# Deneigus_Controle_Soufflante.net
KiCad netlist of a schematic drawn in Altium Designer
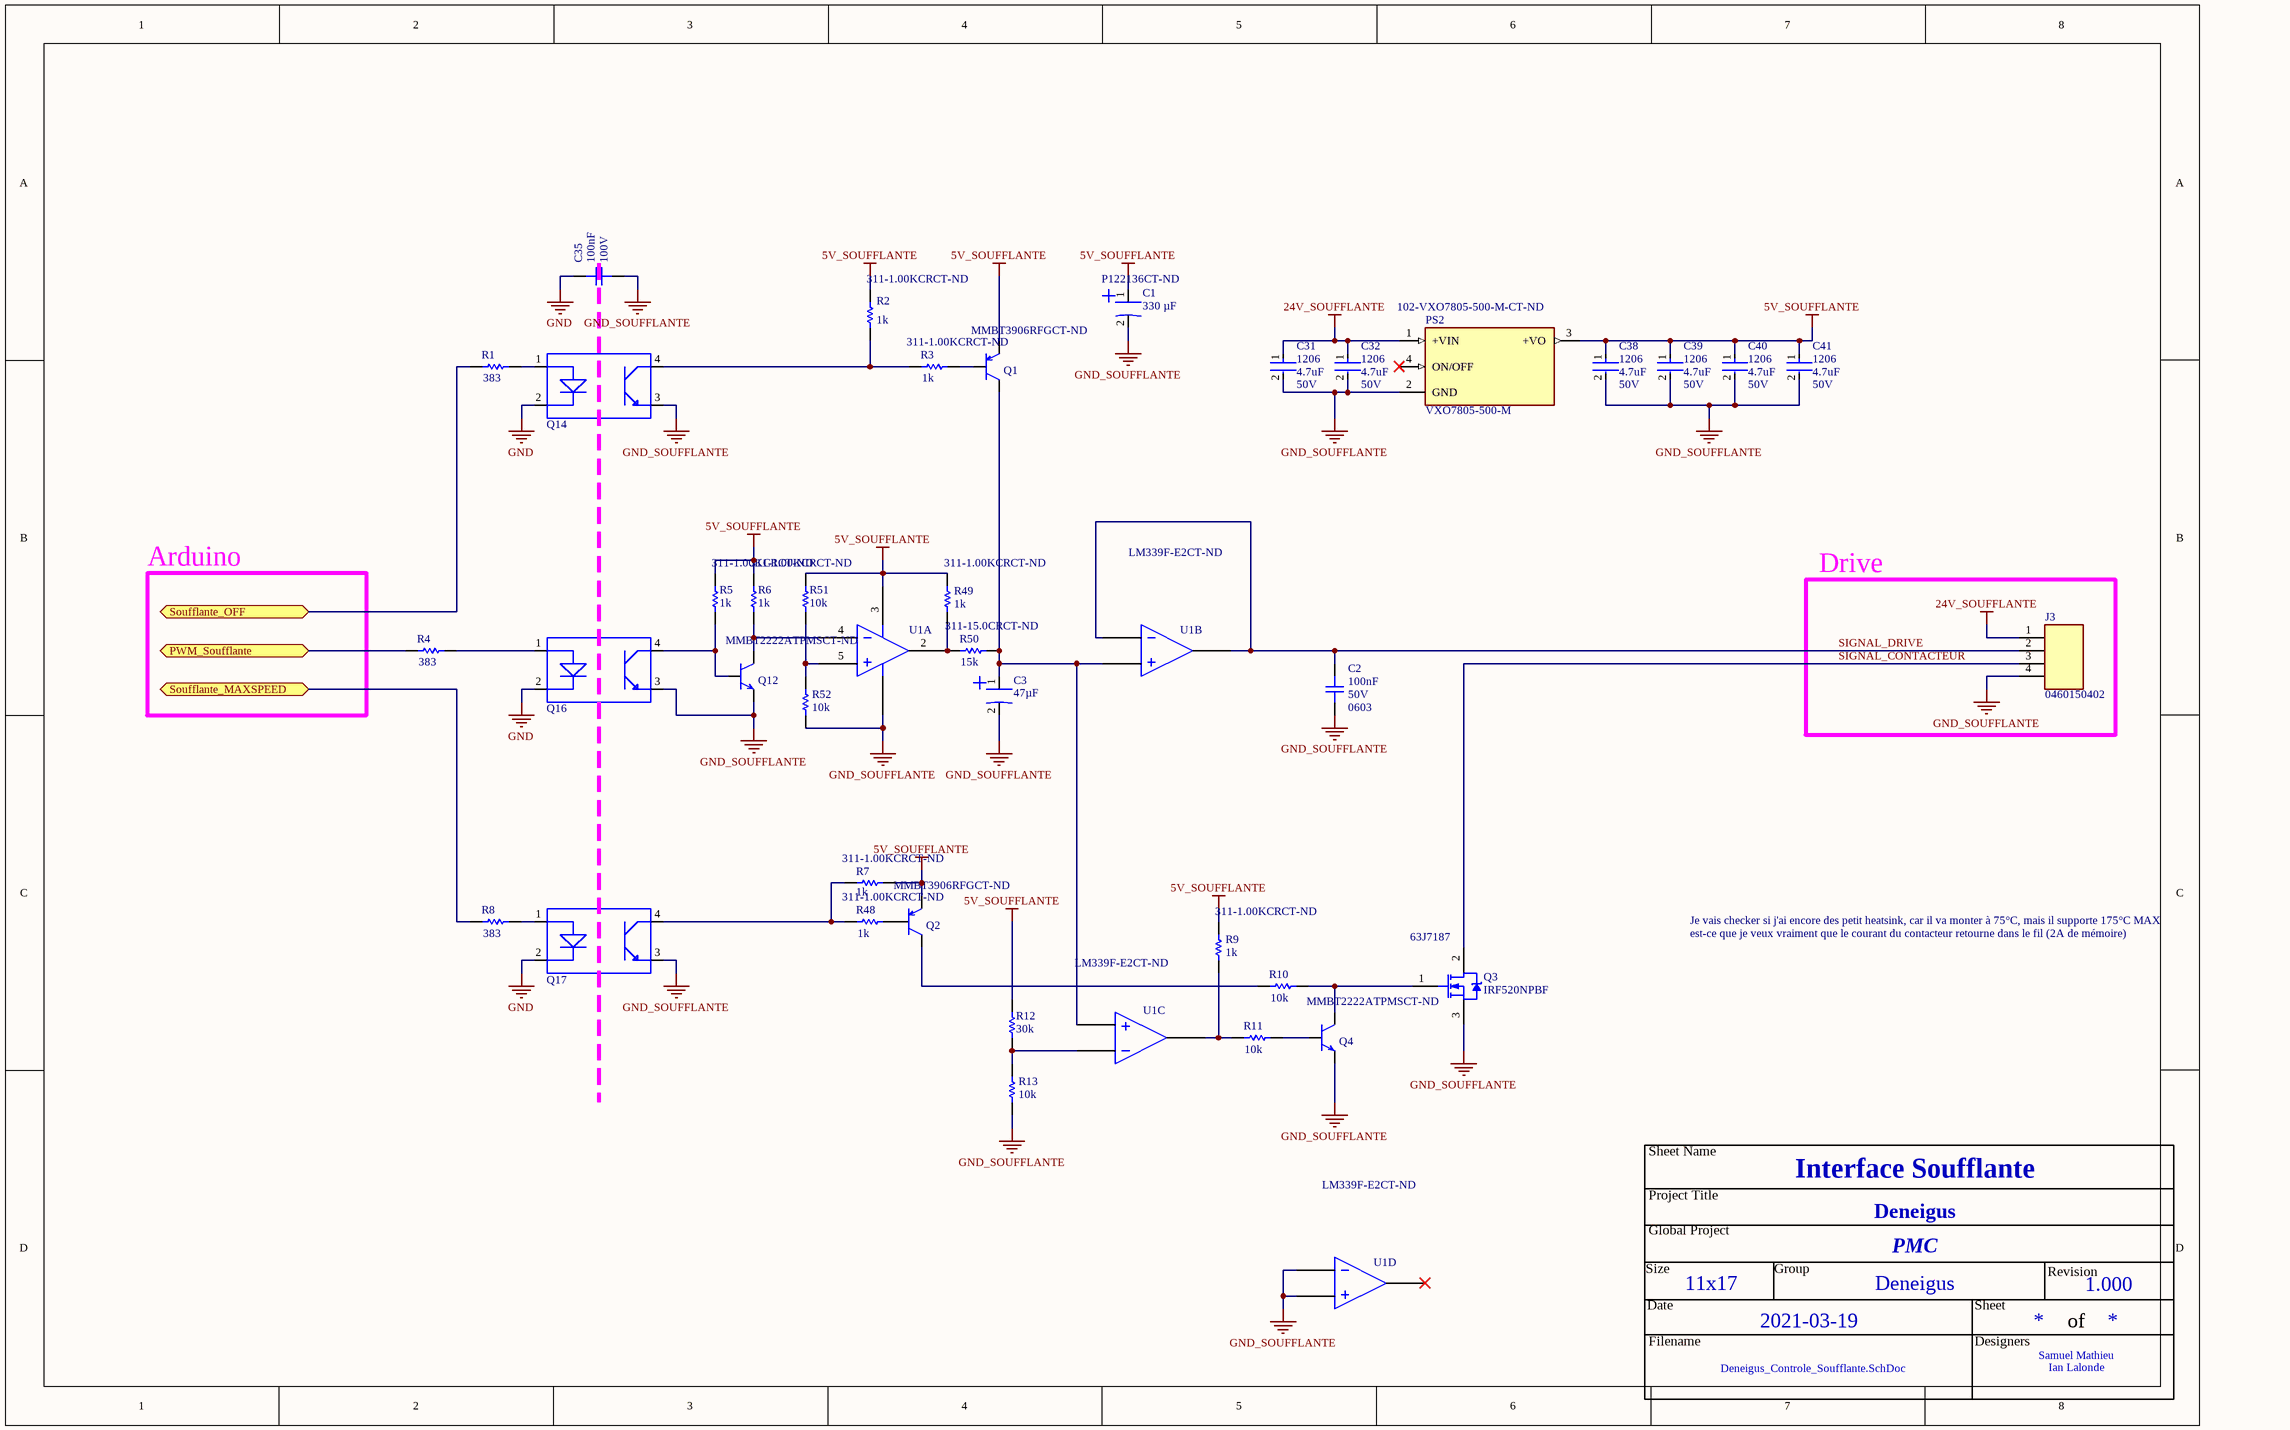
[diagram p0: Deneigus_Controle_Soufflante.SchDoc]

(export (version "E")
  (design (tool "Eeschema 10.0.6"))
  (components
    (comp (ref "C1")
      (value "330 µF")
      (footprint "330uF (10.3x10.3mm)")
      (fields
        (field (name "MFG") "Würth Elektronik")
        (field (name "MFG PART NUMBER") "875105344006")
        (field (name "SUPPLIER PART NUMBER 1") "P122136CT-ND")
        (field (name "Comment") "CAP ALUM POLY 47UF 20% 16V SMD")
      )
      (libsource (lib "S7CAS-APP1") (part "47µF SMD"))
    )
    (comp (ref "C2")
      (value "100nF")
      (footprint "CAP_0603")
      (description "CAP - 0603")
      (fields
        (field (name "VOLTAGE") "50V")
        (field (name "PACKAGE") "0603")
        (field (name "CREATEDBY") "Jonathan Bouchard")
      )
      (libsource (lib "S7CAS_LIB2021") (part "CAP - 0603"))
    )
    (comp (ref "C3")
      (value "47µF")
      (footprint "47uF")
      (fields
        (field (name "MFG") "Würth Elektronik")
        (field (name "MFG PART NUMBER") "875105344006")
        (field (name "Comment") "CAP ALUM POLY 47UF 20% 16V SMD")
      )
      (libsource (lib "S7CAS-APP1") (part "47µF SMD"))
    )
    (comp (ref "C31")
      (value "CL31B475KBHNFNE")
      (footprint "FP-CL31-IPC_C")
      (description "Cap Ceramic 4.7uF 50V X7R ±10% SMD 1206 +125°C Embossed T/R")
      (fields
        (field (name "CASE/PACKAGE") "1206")
        (field (name "VOLTAGE RATING") "50V")
        (field (name "TOLERANCE") "10%")
        (field (name "CAPACITANCE") "4.7uF")
      )
      (libsource (lib "Altium Content Vault") (part "b4654b650e69147ec39a6b967a45e02"))
    )
    (comp (ref "C32")
      (value "CL31B475KBHNFNE")
      (footprint "FP-CL31-IPC_C")
      (description "Cap Ceramic 4.7uF 50V X7R ±10% SMD 1206 +125°C Embossed T/R")
      (fields
        (field (name "CASE/PACKAGE") "1206")
        (field (name "VOLTAGE RATING") "50V")
        (field (name "TOLERANCE") "10%")
        (field (name "CAPACITANCE") "4.7uF")
      )
      (libsource (lib "Altium Content Vault") (part "b4654b650e69147ec39a6b967a45e02"))
    )
    (comp (ref "C35")
      (value "100nF")
      (footprint "CAP_0805")
      (description "CAP - 0805")
      (fields
        (field (name "MFG") "Murata Electronics")
        (field (name "MFG PART NUMBER") "GRM21BR61H106ME43L")
        (field (name "VOLTAGE") "100V")
        (field (name "CREATEDBY") "Jonathan Bouchard")
      )
      (libsource (lib "S7CAS_LIB2021(1)") (part "CAP - 0805"))
    )
    (comp (ref "C38")
      (value "CL31B475KBHNFNE")
      (footprint "FP-CL31-IPC_C")
      (description "Cap Ceramic 4.7uF 50V X7R ±10% SMD 1206 +125°C Embossed T/R")
      (fields
        (field (name "CASE/PACKAGE") "1206")
        (field (name "VOLTAGE RATING") "50V")
        (field (name "TOLERANCE") "10%")
        (field (name "CAPACITANCE") "4.7uF")
      )
      (libsource (lib "Altium Content Vault") (part "b4654b650e69147ec39a6b967a45e02"))
    )
    (comp (ref "C39")
      (value "CL31B475KBHNFNE")
      (footprint "FP-CL31-IPC_C")
      (description "Cap Ceramic 4.7uF 50V X7R ±10% SMD 1206 +125°C Embossed T/R")
      (fields
        (field (name "CASE/PACKAGE") "1206")
        (field (name "VOLTAGE RATING") "50V")
        (field (name "TOLERANCE") "10%")
        (field (name "CAPACITANCE") "4.7uF")
      )
      (libsource (lib "Altium Content Vault") (part "b4654b650e69147ec39a6b967a45e02"))
    )
    (comp (ref "C40")
      (value "CL31B475KBHNFNE")
      (footprint "FP-CL31-IPC_C")
      (description "Cap Ceramic 4.7uF 50V X7R ±10% SMD 1206 +125°C Embossed T/R")
      (fields
        (field (name "CASE/PACKAGE") "1206")
        (field (name "VOLTAGE RATING") "50V")
        (field (name "TOLERANCE") "10%")
        (field (name "CAPACITANCE") "4.7uF")
      )
      (libsource (lib "Altium Content Vault") (part "b4654b650e69147ec39a6b967a45e02"))
    )
    (comp (ref "C41")
      (value "CL31B475KBHNFNE")
      (footprint "FP-CL31-IPC_C")
      (description "Cap Ceramic 4.7uF 50V X7R ±10% SMD 1206 +125°C Embossed T/R")
      (fields
        (field (name "CASE/PACKAGE") "1206")
        (field (name "VOLTAGE RATING") "50V")
        (field (name "TOLERANCE") "10%")
        (field (name "CAPACITANCE") "4.7uF")
      )
      (libsource (lib "Altium Content Vault") (part "b4654b650e69147ec39a6b967a45e02"))
    )
    (comp (ref "J3")
      (value "0460150402")
      (footprint "Molex_4PIN")
      (libsource (lib "S7CAS-APP1") (part "Molex_4PIN"))
    )
    (comp (ref "PS2")
      (value "VXO7805-500-M")
      (footprint "SnapEDApcb:CONV_VXO7805-500-M")
      (description "500 mA Output Current, 4.75~36 Vdc Input, SMT, Non-Isolated, Dc-Dc Converter")
      (fields
        (field (name "MF") "CUI Inc.")
        (field (name "SUPPLIER PART NUMBER 1") "102-VXO7805-500-M-CT-ND")
      )
      (libsource (lib "VXO7805-500-M") (part "VXO7805-500-M"))
    )
    (comp (ref "Q1")
      (value "TRANS PNP 40V 0.2A SOT23")
      (footprint "SOT-23")
      (description "Trans GP BJT PNP 40V 0.2A 3-Pin SOT-23 T/R")
      (fields
        (field (name "MANUFACTURER") "MCC")
        (field (name "MANUFACTURER PART NUMBER") "MMBT3906-TP")
        (field (name "SUPPLIER PART NUMBER 1") "MMBT3906RFGCT-ND")
      )
      (libsource (lib "S7CAS-APP1") (part "PNP 3906 SMD"))
    )
    (comp (ref "Q2")
      (value "TRANS PNP 40V 0.2A SOT23")
      (footprint "SOT-23")
      (description "Trans GP BJT PNP 40V 0.2A 3-Pin SOT-23 T/R")
      (fields
        (field (name "MANUFACTURER") "MCC")
        (field (name "MANUFACTURER PART NUMBER") "MMBT3906-TP")
        (field (name "SUPPLIER PART NUMBER 1") "MMBT3906RFGCT-ND")
      )
      (libsource (lib "S7CAS-APP1") (part "PNP 3906 SMD"))
    )
    (comp (ref "Q3")
      (value "IRF520NPBF")
      (footprint "INTR-TO-220AB-3")
      (description "HEXFET(R) Power MOSFET, 100 V, 9.7 A, 0.2 Ohm, -55 to 175 degC, 3-Pin FM (TO-220AB), RoHS, Tube")
      (fields
        (field (name "POWER") "48W")
        (field (name "MANUFACTURER") "International Rectifier")
        (field (name "SUPPLIER PART NUMBER 1") "63J7187")
      )
      (libsource (lib "Université de Sherbrooke") (part "NEMOS-GDS-3_B"))
    )
    (comp (ref "Q4")
      (value "TRANS NPN 40V 0.2A SOT23")
      (footprint "SOT-23")
      (description "Transistor: 200mA 200mW NPN General-Purpose Amplifier, SOT-23, 7IN. Reel")
      (fields
        (field (name "MANUFACTURER") "MCC")
        (field (name "MANUFACTURER PART NUMBER") "MMBT3904-TP")
        (field (name "SUPPLIER PART NUMBER 1") "MMBT2222ATPMSCT-ND")
      )
      (libsource (lib "S7CAS-APP1") (part "NPN 3904 SMD"))
    )
    (comp (ref "Q12")
      (value "TRANS NPN 40V 0.2A SOT23")
      (footprint "SOT-23")
      (description "Transistor: 200mA 200mW NPN General-Purpose Amplifier, SOT-23, 7IN. Reel")
      (fields
        (field (name "MANUFACTURER") "MCC")
        (field (name "MANUFACTURER PART NUMBER") "MMBT3904-TP")
        (field (name "SUPPLIER PART NUMBER 1") "MMBT2222ATPMSCT-ND")
      )
      (libsource (lib "S7CAS-APP1") (part "NPN 3904 SMD"))
    )
    (comp (ref "Q14")
      (value "WL-OCPT OPTOCOUPLER PHOTOTRANSIS")
      (footprint "WL-OCPT OPTOCOUPLER PHOTOTRANSIS")
      (description "Optoisolator Transistor Output 3750Vrms 1 Channel 4-SOP")
      (libsource (lib "S7CAS-APP1") (part "WL-OCPT OPTOCOUPLER PHOTOTRANSIS"))
    )
    (comp (ref "Q16")
      (value "WL-OCPT OPTOCOUPLER PHOTOTRANSIS")
      (footprint "WL-OCPT OPTOCOUPLER PHOTOTRANSIS")
      (description "Optoisolator Transistor Output 3750Vrms 1 Channel 4-SOP")
      (libsource (lib "S7CAS-APP1") (part "WL-OCPT OPTOCOUPLER PHOTOTRANSIS"))
    )
    (comp (ref "Q17")
      (value "WL-OCPT OPTOCOUPLER PHOTOTRANSIS")
      (footprint "WL-OCPT OPTOCOUPLER PHOTOTRANSIS")
      (description "Optoisolator Transistor Output 3750Vrms 1 Channel 4-SOP")
      (libsource (lib "S7CAS-APP1") (part "WL-OCPT OPTOCOUPLER PHOTOTRANSIS"))
    )
    (comp (ref "R1")
      (value "383")
      (footprint "RES_0805")
      (description "Resistor")
      (fields (field (name "Comment") "Res1") (field (name "PUBLISHER") "Altium Limited"))
      (libsource (lib "Miscellaneous Devices") (part "Res1"))
    )
    (comp (ref "R2")
      (value "1k")
      (footprint "RES_0805")
      (description "Resistor")
      (fields
        (field (name "SUPPLIER PART NUMBER 1") "311-1.00KCRCT-ND")
        (field (name "Comment") "Res1")
        (field (name "PUBLISHER") "Altium Limited")
      )
      (libsource (lib "Miscellaneous Devices") (part "Res1"))
    )
    (comp (ref "R3")
      (value "1k")
      (footprint "RES_0805")
      (description "Resistor")
      (fields
        (field (name "SUPPLIER PART NUMBER 1") "311-1.00KCRCT-ND")
        (field (name "Comment") "Res1")
        (field (name "PUBLISHER") "Altium Limited")
      )
      (libsource (lib "Miscellaneous Devices") (part "Res1"))
    )
    (comp (ref "R4")
      (value "383")
      (footprint "RES_0805")
      (description "Resistor")
      (fields (field (name "Comment") "Res1") (field (name "PUBLISHER") "Altium Limited"))
      (libsource (lib "Miscellaneous Devices") (part "Res1"))
    )
    (comp (ref "R5")
      (value "1k")
      (footprint "RES_0805")
      (description "Resistor")
      (fields
        (field (name "SUPPLIER PART NUMBER 1") "311-1.00KCRCT-ND")
        (field (name "Comment") "Res1")
        (field (name "PUBLISHER") "Altium Limited")
      )
      (libsource (lib "Miscellaneous Devices") (part "Res1"))
    )
    (comp (ref "R6")
      (value "1k")
      (footprint "RES_0805")
      (description "Resistor")
      (fields
        (field (name "SUPPLIER PART NUMBER 1") "311-1.00KCRCT-ND")
        (field (name "Comment") "Res1")
        (field (name "PUBLISHER") "Altium Limited")
      )
      (libsource (lib "Miscellaneous Devices") (part "Res1"))
    )
    (comp (ref "R7")
      (value "1k")
      (footprint "RES_0805")
      (description "Resistor")
      (fields
        (field (name "SUPPLIER PART NUMBER 1") "311-1.00KCRCT-ND")
        (field (name "Comment") "Res1")
        (field (name "PUBLISHER") "Altium Limited")
      )
      (libsource (lib "Miscellaneous Devices") (part "Res1"))
    )
    (comp (ref "R8")
      (value "383")
      (footprint "RES_0805")
      (description "Resistor")
      (fields (field (name "Comment") "Res1") (field (name "PUBLISHER") "Altium Limited"))
      (libsource (lib "Miscellaneous Devices") (part "Res1"))
    )
    (comp (ref "R9")
      (value "1k")
      (footprint "RES_0805")
      (description "Resistor")
      (fields
        (field (name "SUPPLIER PART NUMBER 1") "311-1.00KCRCT-ND")
        (field (name "Comment") "Res1")
        (field (name "PUBLISHER") "Altium Limited")
      )
      (libsource (lib "Miscellaneous Devices") (part "Res1"))
    )
    (comp (ref "R10")
      (value "10k")
      (footprint "RES_0805")
      (description "Resistor")
      (fields (field (name "Comment") "Res1") (field (name "PUBLISHER") "Altium Limited"))
      (libsource (lib "Miscellaneous Devices") (part "Res1"))
    )
    (comp (ref "R11")
      (value "10k")
      (footprint "RES_0805")
      (description "Resistor")
      (fields (field (name "Comment") "Res1") (field (name "PUBLISHER") "Altium Limited"))
      (libsource (lib "Miscellaneous Devices") (part "Res1"))
    )
    (comp (ref "R12")
      (value "30k")
      (footprint "RES_0805")
      (description "Resistor")
      (fields (field (name "Comment") "Res1") (field (name "PUBLISHER") "Altium Limited"))
      (libsource (lib "Miscellaneous Devices") (part "Res1"))
    )
    (comp (ref "R13")
      (value "10k")
      (footprint "RES_0805")
      (description "Resistor")
      (fields (field (name "Comment") "Res1") (field (name "PUBLISHER") "Altium Limited"))
      (libsource (lib "Miscellaneous Devices") (part "Res1"))
    )
    (comp (ref "R48")
      (value "1k")
      (footprint "RES_0805")
      (description "Resistor")
      (fields
        (field (name "SUPPLIER PART NUMBER 1") "311-1.00KCRCT-ND")
        (field (name "Comment") "Res1")
        (field (name "PUBLISHER") "Altium Limited")
      )
      (libsource (lib "Miscellaneous Devices") (part "Res1"))
    )
    (comp (ref "R49")
      (value "1k")
      (footprint "RES_0805")
      (description "Resistor")
      (fields
        (field (name "SUPPLIER PART NUMBER 1") "311-1.00KCRCT-ND")
        (field (name "Comment") "Res1")
        (field (name "PUBLISHER") "Altium Limited")
      )
      (libsource (lib "Miscellaneous Devices") (part "Res1"))
    )
    (comp (ref "R50")
      (value "15k")
      (footprint "RES_0805")
      (description "Resistor")
      (fields
        (field (name "SUPPLIER PART NUMBER 1") "311-15.0CRCT-ND")
        (field (name "Comment") "Res1")
        (field (name "PUBLISHER") "Altium Limited")
      )
      (libsource (lib "Miscellaneous Devices") (part "Res1"))
    )
    (comp (ref "R51")
      (value "10k")
      (footprint "RES_0805")
      (description "Resistor")
      (fields (field (name "Comment") "Res1") (field (name "PUBLISHER") "Altium Limited"))
      (libsource (lib "Miscellaneous Devices") (part "Res1"))
    )
    (comp (ref "R52")
      (value "10k")
      (footprint "RES_0805")
      (description "Resistor")
      (fields (field (name "Comment") "Res1") (field (name "PUBLISHER") "Altium Limited"))
      (libsource (lib "Miscellaneous Devices") (part "Res1"))
    )
    (comp (ref "U1")
      (value "LM339")
      (footprint "SOP14")
      (description "Comparator Quad ±16V/32V 14-Pin SOP T/R")
      (fields
        (field (name "VOLTAGE") "1.14 V ~ 1.26 V")
        (field (name "MFG") "Rohm Semiconductor")
        (field (name "SUPPLIER PART NUMBER 2") "LM339F-E2CT-ND")
        (field (name "CREATEDBY") "Samuel Mathieu")
      )
      (libsource (lib "S7CAS-APP1") (part "LM339"))
    )
  )
  (nets
    (net (code "1") (name "/PWM_Soufflante") (class "Default")
      (node (ref "R4") (pin "1") (pinfunction "1_1") (pintype "passive"))
    )
    (net (code "2") (name "/SIGNAL_CONTACTEUR") (class "Default")
      (node (ref "J3") (pin "3") (pinfunction "3_3") (pintype "passive"))
      (node (ref "Q3") (pin "2") (pinfunction "D_2") (pintype "passive"))
    )
    (net (code "3") (name "/SIGNAL_DRIVE") (class "Default")
      (node (ref "C2") (pin "2") (pinfunction "2_2") (pintype "passive"))
      (node (ref "J3") (pin "2") (pinfunction "2_2") (pintype "passive"))
      (node (ref "U1") (pin "1") (pinfunction "1_1") (pintype "passive"))
      (node (ref "U1") (pin "6") (pinfunction "6_6") (pintype "passive"))
    )
    (net (code "4") (name "/Soufflante_MAXSPEED") (class "Default")
      (node (ref "R8") (pin "1") (pinfunction "1_1") (pintype "passive"))
    )
    (net (code "5") (name "/Soufflante_OFF") (class "Default")
      (node (ref "R1") (pin "1") (pinfunction "1_1") (pintype "passive"))
    )
    (net (code "6") (name "5V_SOUFFLANTE") (class "Default")
      (node (ref "C1") (pin "1") (pinfunction "1_1") (pintype "passive"))
      (node (ref "C38") (pin "1") (pinfunction "1_1") (pintype "passive"))
      (node (ref "C39") (pin "1") (pinfunction "1_1") (pintype "passive"))
      (node (ref "C40") (pin "1") (pinfunction "1_1") (pintype "passive"))
      (node (ref "C41") (pin "1") (pinfunction "1_1") (pintype "passive"))
      (node (ref "PS2") (pin "3") (pinfunction "+VO_3") (pintype "output"))
      (node (ref "Q1") (pin "2") (pinfunction "2_2") (pintype "passive"))
      (node (ref "Q2") (pin "2") (pinfunction "2_2") (pintype "passive"))
      (node (ref "R12") (pin "2") (pinfunction "2_2") (pintype "passive"))
      (node (ref "R2") (pin "1") (pinfunction "1_1") (pintype "passive"))
      (node (ref "R49") (pin "1") (pinfunction "1_1") (pintype "passive"))
      (node (ref "R5") (pin "2") (pinfunction "2_2") (pintype "passive"))
      (node (ref "R51") (pin "2") (pinfunction "2_2") (pintype "passive"))
      (node (ref "R6") (pin "2") (pinfunction "2_2") (pintype "passive"))
      (node (ref "R7") (pin "1") (pinfunction "1_1") (pintype "passive"))
      (node (ref "R9") (pin "2") (pinfunction "2_2") (pintype "passive"))
      (node (ref "U1") (pin "3") (pinfunction "3_3") (pintype "passive"))
    )
    (net (code "7") (name "24V_SOUFFLANTE") (class "Default")
      (node (ref "C31") (pin "1") (pinfunction "1_1") (pintype "passive"))
      (node (ref "C32") (pin "1") (pinfunction "1_1") (pintype "passive"))
      (node (ref "J3") (pin "1") (pinfunction "1_1") (pintype "passive"))
      (node (ref "PS2") (pin "1") (pinfunction "+VIN_1") (pintype "input"))
    )
    (net (code "8") (name "GND") (class "Default")
      (node (ref "C35") (pin "2") (pinfunction "2_2") (pintype "passive"))
      (node (ref "Q14") (pin "2") (pinfunction "2_2") (pintype "passive"))
      (node (ref "Q16") (pin "2") (pinfunction "2_2") (pintype "passive"))
      (node (ref "Q17") (pin "2") (pinfunction "2_2") (pintype "passive"))
    )
    (net (code "9") (name "GND_SOUFFLANTE") (class "Default")
      (node (ref "C1") (pin "2") (pinfunction "2_2") (pintype "passive"))
      (node (ref "C2") (pin "1") (pinfunction "1_1") (pintype "passive"))
      (node (ref "C3") (pin "2") (pinfunction "2_2") (pintype "passive"))
      (node (ref "C31") (pin "2") (pinfunction "2_2") (pintype "passive"))
      (node (ref "C32") (pin "2") (pinfunction "2_2") (pintype "passive"))
      (node (ref "C35") (pin "1") (pinfunction "1_1") (pintype "passive"))
      (node (ref "C38") (pin "2") (pinfunction "2_2") (pintype "passive"))
      (node (ref "C39") (pin "2") (pinfunction "2_2") (pintype "passive"))
      (node (ref "C40") (pin "2") (pinfunction "2_2") (pintype "passive"))
      (node (ref "C41") (pin "2") (pinfunction "2_2") (pintype "passive"))
      (node (ref "J3") (pin "4") (pinfunction "4_4") (pintype "passive"))
      (node (ref "PS2") (pin "2") (pinfunction "GND_2") (pintype "power_in"))
      (node (ref "Q12") (pin "2") (pinfunction "2_2") (pintype "passive"))
      (node (ref "Q14") (pin "3") (pinfunction "3_3") (pintype "passive"))
      (node (ref "Q16") (pin "3") (pinfunction "3_3") (pintype "passive"))
      (node (ref "Q17") (pin "3") (pinfunction "3_3") (pintype "passive"))
      (node (ref "Q3") (pin "3") (pinfunction "S_3") (pintype "passive"))
      (node (ref "Q4") (pin "2") (pinfunction "2_2") (pintype "passive"))
      (node (ref "R13") (pin "1") (pinfunction "1_1") (pintype "passive"))
      (node (ref "R52") (pin "1") (pinfunction "1_1") (pintype "passive"))
      (node (ref "U1") (pin "10") (pinfunction "10_10") (pintype "passive"))
      (node (ref "U1") (pin "11") (pinfunction "11_11") (pintype "passive"))
      (node (ref "U1") (pin "12") (pinfunction "12_12") (pintype "passive"))
    )
    (net (code "10") (name "Net-(C3-Pad1)") (class "Default")
      (node (ref "C3") (pin "1") (pinfunction "1_1") (pintype "passive"))
      (node (ref "Q1") (pin "3") (pinfunction "3_3") (pintype "passive"))
      (node (ref "R50") (pin "2") (pinfunction "2_2") (pintype "passive"))
      (node (ref "U1") (pin "7") (pinfunction "7_7") (pintype "passive"))
      (node (ref "U1") (pin "9") (pinfunction "9_9") (pintype "passive"))
    )
    (net (code "11") (name "Net-(Q1-Pad1)") (class "Default")
      (node (ref "Q1") (pin "1") (pinfunction "1_1") (pintype "passive"))
      (node (ref "R3") (pin "2") (pinfunction "2_2") (pintype "passive"))
    )
    (net (code "12") (name "Net-(Q2-Pad1)") (class "Default")
      (node (ref "Q2") (pin "1") (pinfunction "1_1") (pintype "passive"))
      (node (ref "R48") (pin "2") (pinfunction "2_2") (pintype "passive"))
    )
    (net (code "13") (name "Net-(Q2-Pad3)") (class "Default")
      (node (ref "Q2") (pin "3") (pinfunction "3_3") (pintype "passive"))
      (node (ref "R10") (pin "2") (pinfunction "2_2") (pintype "passive"))
    )
    (net (code "14") (name "Net-(Q3-G)") (class "Default")
      (node (ref "Q3") (pin "1") (pinfunction "G_1") (pintype "passive"))
      (node (ref "Q4") (pin "3") (pinfunction "3_3") (pintype "passive"))
      (node (ref "R10") (pin "1") (pinfunction "1_1") (pintype "passive"))
    )
    (net (code "15") (name "Net-(Q4-Pad1)") (class "Default")
      (node (ref "Q4") (pin "1") (pinfunction "1_1") (pintype "passive"))
      (node (ref "R11") (pin "2") (pinfunction "2_2") (pintype "passive"))
    )
    (net (code "16") (name "Net-(Q12-Pad1)") (class "Default")
      (node (ref "Q12") (pin "1") (pinfunction "1_1") (pintype "passive"))
      (node (ref "Q16") (pin "4") (pinfunction "4_4") (pintype "passive"))
      (node (ref "R5") (pin "1") (pinfunction "1_1") (pintype "passive"))
    )
    (net (code "17") (name "Net-(Q12-Pad3)") (class "Default")
      (node (ref "Q12") (pin "3") (pinfunction "3_3") (pintype "passive"))
      (node (ref "R6") (pin "1") (pinfunction "1_1") (pintype "passive"))
      (node (ref "U1") (pin "4") (pinfunction "4_4") (pintype "passive"))
    )
    (net (code "18") (name "Net-(Q14-Pad1)") (class "Default")
      (node (ref "Q14") (pin "1") (pinfunction "1_1") (pintype "passive"))
      (node (ref "R1") (pin "2") (pinfunction "2_2") (pintype "passive"))
    )
    (net (code "19") (name "Net-(Q14-Pad4)") (class "Default")
      (node (ref "Q14") (pin "4") (pinfunction "4_4") (pintype "passive"))
      (node (ref "R2") (pin "2") (pinfunction "2_2") (pintype "passive"))
      (node (ref "R3") (pin "1") (pinfunction "1_1") (pintype "passive"))
    )
    (net (code "20") (name "Net-(Q16-Pad1)") (class "Default")
      (node (ref "Q16") (pin "1") (pinfunction "1_1") (pintype "passive"))
      (node (ref "R4") (pin "2") (pinfunction "2_2") (pintype "passive"))
    )
    (net (code "21") (name "Net-(Q17-Pad1)") (class "Default")
      (node (ref "Q17") (pin "1") (pinfunction "1_1") (pintype "passive"))
      (node (ref "R8") (pin "2") (pinfunction "2_2") (pintype "passive"))
    )
    (net (code "22") (name "Net-(Q17-Pad4)") (class "Default")
      (node (ref "Q17") (pin "4") (pinfunction "4_4") (pintype "passive"))
      (node (ref "R48") (pin "1") (pinfunction "1_1") (pintype "passive"))
      (node (ref "R7") (pin "2") (pinfunction "2_2") (pintype "passive"))
    )
    (net (code "23") (name "Net-(R11-Pad1)") (class "Default")
      (node (ref "R11") (pin "1") (pinfunction "1_1") (pintype "passive"))
      (node (ref "R9") (pin "1") (pinfunction "1_1") (pintype "passive"))
      (node (ref "U1") (pin "14") (pinfunction "14_14") (pintype "passive"))
    )
    (net (code "24") (name "Net-(R12-Pad1)") (class "Default")
      (node (ref "R12") (pin "1") (pinfunction "1_1") (pintype "passive"))
      (node (ref "R13") (pin "2") (pinfunction "2_2") (pintype "passive"))
      (node (ref "U1") (pin "8") (pinfunction "8_8") (pintype "passive"))
    )
    (net (code "25") (name "Net-(R49-Pad2)") (class "Default")
      (node (ref "R49") (pin "2") (pinfunction "2_2") (pintype "passive"))
      (node (ref "R50") (pin "1") (pinfunction "1_1") (pintype "passive"))
      (node (ref "U1") (pin "2") (pinfunction "2_2") (pintype "passive"))
    )
    (net (code "26") (name "Net-(R51-Pad1)") (class "Default")
      (node (ref "R51") (pin "1") (pinfunction "1_1") (pintype "passive"))
      (node (ref "R52") (pin "2") (pinfunction "2_2") (pintype "passive"))
      (node (ref "U1") (pin "5") (pinfunction "5_5") (pintype "passive"))
    )
    (net (code "27") (name "unconnected-(PS2-ON{slash}OFF-Pad4)") (class "Default")
      (node (ref "PS2") (pin "4") (pinfunction "ON/OFF_4") (pintype "input+no_connect"))
    )
    (net (code "28") (name "unconnected-(U1-Pad13)") (class "Default")
      (node (ref "U1") (pin "13") (pinfunction "13_13") (pintype "passive+no_connect"))
    )
  )
)
